# BOTTOM_pcb_redonda_definitiva.net
KiCad netlist of a schematic drawn in EAGLE
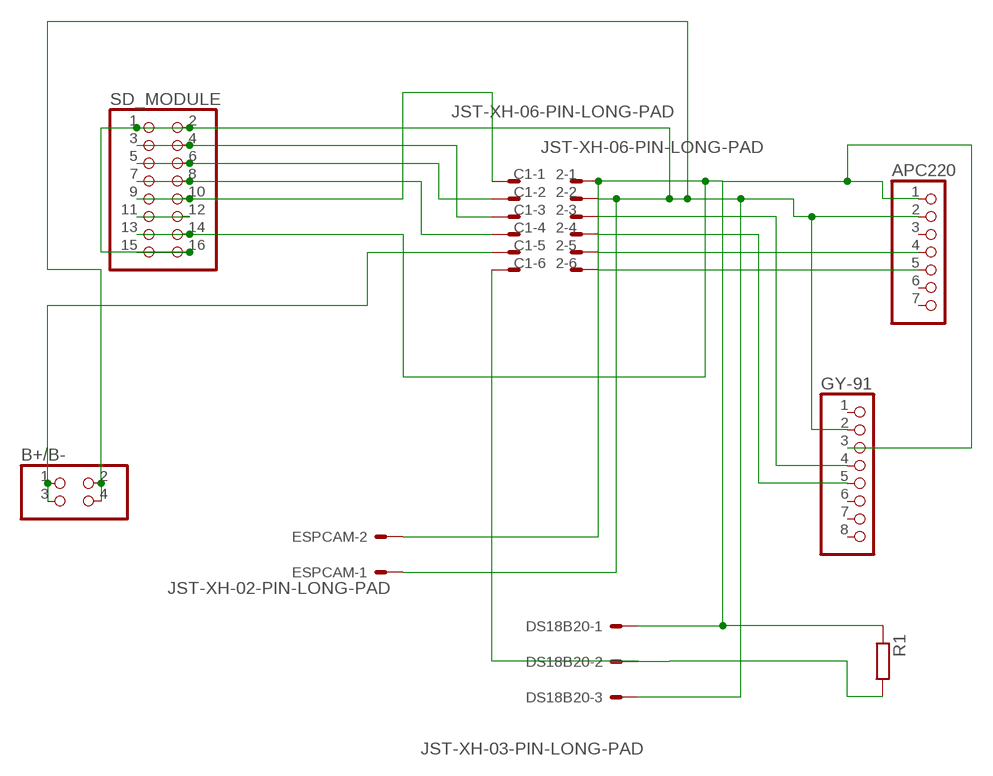
[diagram p0: schematic, sheet 1]

(export (version "E")
  (design (tool "Eeschema 10.0.6"))
  (components
    (comp (ref "2")
      (value "JST-XH-06-PIN-LONG-PAD")
      (footprint "eagle-import:JST-XH-06-PACKAGE-LONG-PAD")
      (libsource (lib "eagle-import") (part "JST-XH-06-PIN-LONG-PAD"))
    )
    (comp (ref "APC220")
      (value "PINHD-1X7")
      (footprint "eagle-import:1X07")
      (libsource (lib "eagle-import") (part "PINHD-1X7"))
    )
    (comp (ref "B+/B-")
      (value "PINHD-2X2")
      (footprint "eagle-import:2X02")
      (libsource (lib "eagle-import") (part "PINHD-2X2"))
    )
    (comp (ref "C1")
      (value "JST-XH-06-PIN-LONG-PAD")
      (footprint "eagle-import:JST-XH-06-PACKAGE-LONG-PAD")
      (libsource (lib "eagle-import") (part "JST-XH-06-PIN-LONG-PAD"))
    )
    (comp (ref "DS18B20")
      (value "JST-XH-03-PIN-LONG-PAD")
      (footprint "eagle-import:JST-XH-03-PACKAGE-LONG-PAD")
      (libsource (lib "eagle-import") (part "JST-XH-03-PIN-LONG-PAD"))
    )
    (comp (ref "ESPCAM")
      (value "JST-XH-02-PIN-LONG-PAD")
      (footprint "eagle-import:JST-XH-02-PACKAGE-LONG-PAD")
      (libsource (lib "eagle-import") (part "JST-XH-02-PIN-LONG-PAD"))
    )
    (comp (ref "GY-91")
      (value "PINHD-1X8")
      (footprint "eagle-import:1X08")
      (libsource (lib "eagle-import") (part "PINHD-1X8"))
    )
    (comp (ref "R1")
      (value "R-EU_0207/10")
      (footprint "eagle-import:0207_10")
      (libsource (lib "eagle-import") (part "R-EU_0207/10"))
    )
    (comp (ref "SD_MODULE")
      (value "PINHD-2X8")
      (footprint "eagle-import:2X08")
      (libsource (lib "eagle-import") (part "PINHD-2X8"))
    )
  )
  (nets
    (net (code "1") (name "Net-(2A-S)") (class "Default")
      (node (ref "2") (pin "1") (pinfunction "S_1") (pintype "passive"))
      (node (ref "APC220") (pin "1") (pinfunction "1_1") (pintype "passive"))
      (node (ref "DS18B20") (pin "1") (pinfunction "S_1") (pintype "passive"))
      (node (ref "ESPCAM") (pin "2") (pinfunction "S_2") (pintype "passive"))
      (node (ref "GY-91") (pin "3") (pinfunction "3_3") (pintype "passive"))
      (node (ref "R1") (pin "1") (pinfunction "1_1") (pintype "passive"))
      (node (ref "SD_MODULE") (pin "13") (pinfunction "13_13") (pintype "passive"))
      (node (ref "SD_MODULE") (pin "14") (pinfunction "14_14") (pintype "passive"))
    )
    (net (code "2") (name "Net-(2B-S)") (class "Default")
      (node (ref "2") (pin "2") (pinfunction "S_2") (pintype "passive"))
      (node (ref "APC220") (pin "2") (pinfunction "2_2") (pintype "passive"))
      (node (ref "B+/B-") (pin "2") (pinfunction "2_2") (pintype "passive"))
      (node (ref "B+/B-") (pin "4") (pinfunction "4_4") (pintype "passive"))
      (node (ref "DS18B20") (pin "3") (pinfunction "S_3") (pintype "passive"))
      (node (ref "ESPCAM") (pin "1") (pinfunction "S_1") (pintype "passive"))
      (node (ref "GY-91") (pin "2") (pinfunction "2_2") (pintype "passive"))
      (node (ref "SD_MODULE") (pin "1") (pinfunction "1_1") (pintype "passive"))
      (node (ref "SD_MODULE") (pin "15") (pinfunction "15_15") (pintype "passive"))
      (node (ref "SD_MODULE") (pin "16") (pinfunction "16_16") (pintype "passive"))
      (node (ref "SD_MODULE") (pin "2") (pinfunction "2_2") (pintype "passive"))
    )
    (net (code "3") (name "Net-(2C-S)") (class "Default")
      (node (ref "2") (pin "3") (pinfunction "S_3") (pintype "passive"))
      (node (ref "GY-91") (pin "4") (pinfunction "4_4") (pintype "passive"))
    )
    (net (code "4") (name "Net-(2D-S)") (class "Default")
      (node (ref "2") (pin "4") (pinfunction "S_4") (pintype "passive"))
      (node (ref "GY-91") (pin "5") (pinfunction "5_5") (pintype "passive"))
    )
    (net (code "5") (name "Net-(2E-S)") (class "Default")
      (node (ref "2") (pin "5") (pinfunction "S_5") (pintype "passive"))
      (node (ref "APC220") (pin "4") (pinfunction "4_4") (pintype "passive"))
    )
    (net (code "6") (name "Net-(2F-S)") (class "Default")
      (node (ref "2") (pin "6") (pinfunction "S_6") (pintype "passive"))
      (node (ref "APC220") (pin "5") (pinfunction "5_5") (pintype "passive"))
    )
    (net (code "7") (name "Net-(C1A-S)") (class "Default")
      (node (ref "C1") (pin "1") (pinfunction "S_1") (pintype "passive"))
      (node (ref "SD_MODULE") (pin "10") (pinfunction "10_10") (pintype "passive"))
      (node (ref "SD_MODULE") (pin "9") (pinfunction "9_9") (pintype "passive"))
    )
    (net (code "8") (name "Net-(C1B-S)") (class "Default")
      (node (ref "C1") (pin "2") (pinfunction "S_2") (pintype "passive"))
      (node (ref "SD_MODULE") (pin "5") (pinfunction "5_5") (pintype "passive"))
      (node (ref "SD_MODULE") (pin "6") (pinfunction "6_6") (pintype "passive"))
    )
    (net (code "9") (name "Net-(C1C-S)") (class "Default")
      (node (ref "C1") (pin "3") (pinfunction "S_3") (pintype "passive"))
      (node (ref "SD_MODULE") (pin "3") (pinfunction "3_3") (pintype "passive"))
      (node (ref "SD_MODULE") (pin "4") (pinfunction "4_4") (pintype "passive"))
    )
    (net (code "10") (name "Net-(C1D-S)") (class "Default")
      (node (ref "C1") (pin "4") (pinfunction "S_4") (pintype "passive"))
      (node (ref "SD_MODULE") (pin "7") (pinfunction "7_7") (pintype "passive"))
      (node (ref "SD_MODULE") (pin "8") (pinfunction "8_8") (pintype "passive"))
    )
    (net (code "11") (name "Net-(C1E-S)") (class "Default")
      (node (ref "B+/B-") (pin "1") (pinfunction "1_1") (pintype "passive"))
      (node (ref "B+/B-") (pin "3") (pinfunction "3_3") (pintype "passive"))
      (node (ref "C1") (pin "5") (pinfunction "S_5") (pintype "passive"))
    )
    (net (code "12") (name "Net-(C1F-S)") (class "Default")
      (node (ref "C1") (pin "6") (pinfunction "S_6") (pintype "passive"))
      (node (ref "DS18B20") (pin "2") (pinfunction "S_2") (pintype "passive"))
      (node (ref "R1") (pin "2") (pinfunction "2_2") (pintype "passive"))
    )
    (net (code "13") (name "Net-(SD_MODULE-Pad11)") (class "Default")
      (node (ref "SD_MODULE") (pin "11") (pinfunction "11_11") (pintype "passive"))
      (node (ref "SD_MODULE") (pin "12") (pinfunction "12_12") (pintype "passive"))
    )
    (net (code "14") (name "unconnected-(APC220-Pad3)") (class "Default")
      (node (ref "APC220") (pin "3") (pinfunction "3_3") (pintype "passive"))
    )
    (net (code "15") (name "unconnected-(APC220-Pad6)") (class "Default")
      (node (ref "APC220") (pin "6") (pinfunction "6_6") (pintype "passive"))
    )
    (net (code "16") (name "unconnected-(APC220-Pad7)") (class "Default")
      (node (ref "APC220") (pin "7") (pinfunction "7_7") (pintype "passive"))
    )
    (net (code "17") (name "unconnected-(GY-91-Pad1)") (class "Default")
      (node (ref "GY-91") (pin "1") (pinfunction "1_1") (pintype "passive"))
    )
    (net (code "18") (name "unconnected-(GY-91-Pad6)") (class "Default")
      (node (ref "GY-91") (pin "6") (pinfunction "6_6") (pintype "passive"))
    )
    (net (code "19") (name "unconnected-(GY-91-Pad7)") (class "Default")
      (node (ref "GY-91") (pin "7") (pinfunction "7_7") (pintype "passive"))
    )
    (net (code "20") (name "unconnected-(GY-91-Pad8)") (class "Default")
      (node (ref "GY-91") (pin "8") (pinfunction "8_8") (pintype "passive"))
    )
  )
)
